# 02_Connectors.net
KiCad netlist of a schematic drawn in Altium Designer
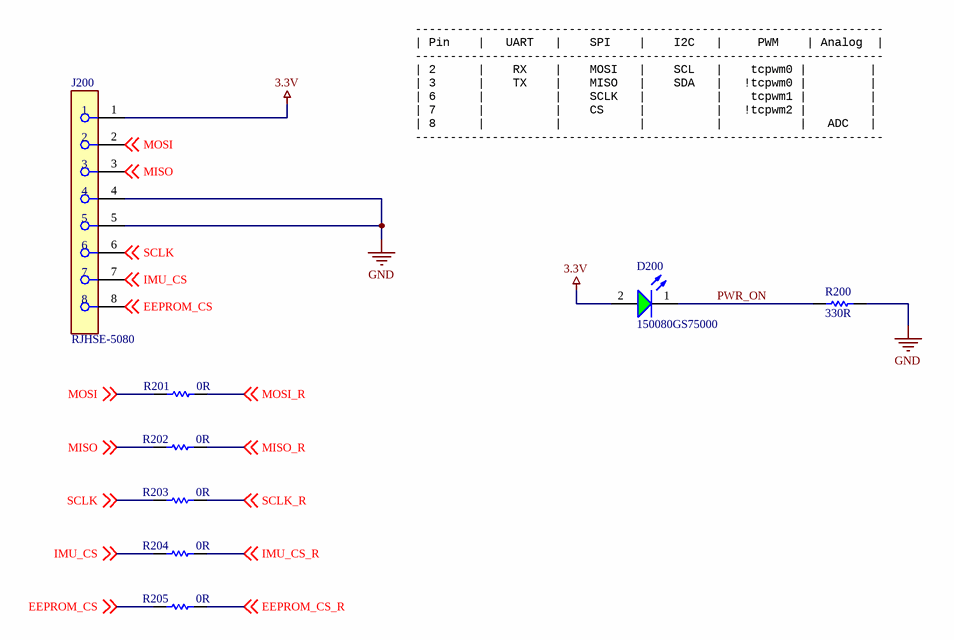
[diagram p0: 02_Connectors.SchDoc]

(export (version "E")
  (design (tool "Eeschema 10.0.6"))
  (components
    (comp (ref "D200")
      (value "150080GS75000")
      (footprint "WL-SMCW_0805_150080xx75000")
      (fields (field (name "MANUFACTURER") "Wurth Electronics"))
      (libsource (lib "Altium Content Vault") (part "LED_Green_2A-1K"))
    )
    (comp (ref "J200")
      (value "RJHSE-5080")
      (footprint "FP-RJHSE-5080-MFG")
      (description "CONN MOD JACK 8P8C R/A UNSHLD")
      (fields
        (field (name "OCTOPART") "https://octopart.com/rjhse-5080-amphenol-45060")
        (field (name "MANUFACTURER") "Amphenol")
      )
      (libsource (lib "Altium Content Vault") (part "b0a0b555dd3abf3683e7c330df25cc4"))
    )
    (comp (ref "R200")
      (value "330R")
      (footprint "RESC2013X60X40LL20T25")
      (fields
        (field (name "MANUFACTURER") "Panasonic")
        (field (name "PART NUMBER") "ERA6AEB331V")
        (field (name "MANUFACTURER PART NUMBER") "ERA-6AEB331V")
      )
      (libsource (lib "Altium Content Vault") (part "RES"))
    )
    (comp (ref "R201")
      (value "0R")
      (footprint "RESC2013X70X40NL20T20")
      (description "Chip Resistor, 0 Ohm, +/- 1%, 0.125 W, -55 to 155 degC, 0805 (2012 Metric), RoHS, Tape and Reel")
      (fields (field (name "PARTNUMBER") "ERJ-6GEY0R00V") (field (name "TOLERANCE") "5%"))
      (libsource (lib "Altium Content Vault") (part "RES-2"))
    )
    (comp (ref "R202")
      (value "0R")
      (footprint "RESC2013X70X40NL20T20")
      (description "Chip Resistor, 0 Ohm, +/- 1%, 0.125 W, -55 to 155 degC, 0805 (2012 Metric), RoHS, Tape and Reel")
      (fields (field (name "PARTNUMBER") "ERJ-6GEY0R00V") (field (name "TOLERANCE") "5%"))
      (libsource (lib "Altium Content Vault") (part "RES-2"))
    )
    (comp (ref "R203")
      (value "0R")
      (footprint "RESC2013X70X40NL20T20")
      (description "Chip Resistor, 0 Ohm, +/- 1%, 0.125 W, -55 to 155 degC, 0805 (2012 Metric), RoHS, Tape and Reel")
      (fields (field (name "PARTNUMBER") "ERJ-6GEY0R00V") (field (name "TOLERANCE") "5%"))
      (libsource (lib "Altium Content Vault") (part "RES-2"))
    )
    (comp (ref "R204")
      (value "0R")
      (footprint "RESC2013X70X40NL20T20")
      (description "Chip Resistor, 0 Ohm, +/- 1%, 0.125 W, -55 to 155 degC, 0805 (2012 Metric), RoHS, Tape and Reel")
      (fields (field (name "PARTNUMBER") "ERJ-6GEY0R00V") (field (name "TOLERANCE") "5%"))
      (libsource (lib "Altium Content Vault") (part "RES-2"))
    )
    (comp (ref "R205")
      (value "0R")
      (footprint "RESC2013X70X40NL20T20")
      (description "Chip Resistor, 0 Ohm, +/- 1%, 0.125 W, -55 to 155 degC, 0805 (2012 Metric), RoHS, Tape and Reel")
      (fields (field (name "PARTNUMBER") "ERJ-6GEY0R00V") (field (name "TOLERANCE") "5%"))
      (libsource (lib "Altium Content Vault") (part "RES-2"))
    )
  )
  (nets
    (net (code "1") (name "/PWR_ON") (class "Default")
      (node (ref "D200") (pin "1") (pinfunction "K_1") (pintype "passive"))
      (node (ref "R200") (pin "1") (pinfunction "1_1") (pintype "passive"))
    )
    (net (code "2") (name "3.3V") (class "Default")
      (node (ref "D200") (pin "2") (pinfunction "A_2") (pintype "passive"))
      (node (ref "J200") (pin "1") (pinfunction "1_1") (pintype "passive"))
    )
    (net (code "3") (name "EEPROM_CS") (class "Default")
      (node (ref "J200") (pin "8") (pinfunction "8_8") (pintype "passive"))
      (node (ref "R205") (pin "1") (pinfunction "1_1") (pintype "passive"))
    )
    (net (code "4") (name "EEPROM_CS_R") (class "Default")
      (node (ref "R205") (pin "2") (pinfunction "2_2") (pintype "passive"))
    )
    (net (code "5") (name "GND") (class "Default")
      (node (ref "J200") (pin "4") (pinfunction "4_4") (pintype "passive"))
      (node (ref "J200") (pin "5") (pinfunction "5_5") (pintype "passive"))
      (node (ref "R200") (pin "2") (pinfunction "2_2") (pintype "passive"))
    )
    (net (code "6") (name "IMU_CS") (class "Default")
      (node (ref "J200") (pin "7") (pinfunction "7_7") (pintype "passive"))
      (node (ref "R204") (pin "1") (pinfunction "1_1") (pintype "passive"))
    )
    (net (code "7") (name "IMU_CS_R") (class "Default")
      (node (ref "R204") (pin "2") (pinfunction "2_2") (pintype "passive"))
    )
    (net (code "8") (name "MISO") (class "Default")
      (node (ref "J200") (pin "3") (pinfunction "3_3") (pintype "passive"))
      (node (ref "R202") (pin "1") (pinfunction "1_1") (pintype "passive"))
    )
    (net (code "9") (name "MISO_R") (class "Default")
      (node (ref "R202") (pin "2") (pinfunction "2_2") (pintype "passive"))
    )
    (net (code "10") (name "MOSI") (class "Default")
      (node (ref "J200") (pin "2") (pinfunction "2_2") (pintype "passive"))
      (node (ref "R201") (pin "1") (pinfunction "1_1") (pintype "passive"))
    )
    (net (code "11") (name "MOSI_R") (class "Default")
      (node (ref "R201") (pin "2") (pinfunction "2_2") (pintype "passive"))
    )
    (net (code "12") (name "SCLK") (class "Default")
      (node (ref "J200") (pin "6") (pinfunction "6_6") (pintype "passive"))
      (node (ref "R203") (pin "1") (pinfunction "1_1") (pintype "passive"))
    )
    (net (code "13") (name "SCLK_R") (class "Default")
      (node (ref "R203") (pin "2") (pinfunction "2_2") (pintype "passive"))
    )
  )
)
